# Ethernet.net
KiCad netlist of a schematic drawn in Altium Designer
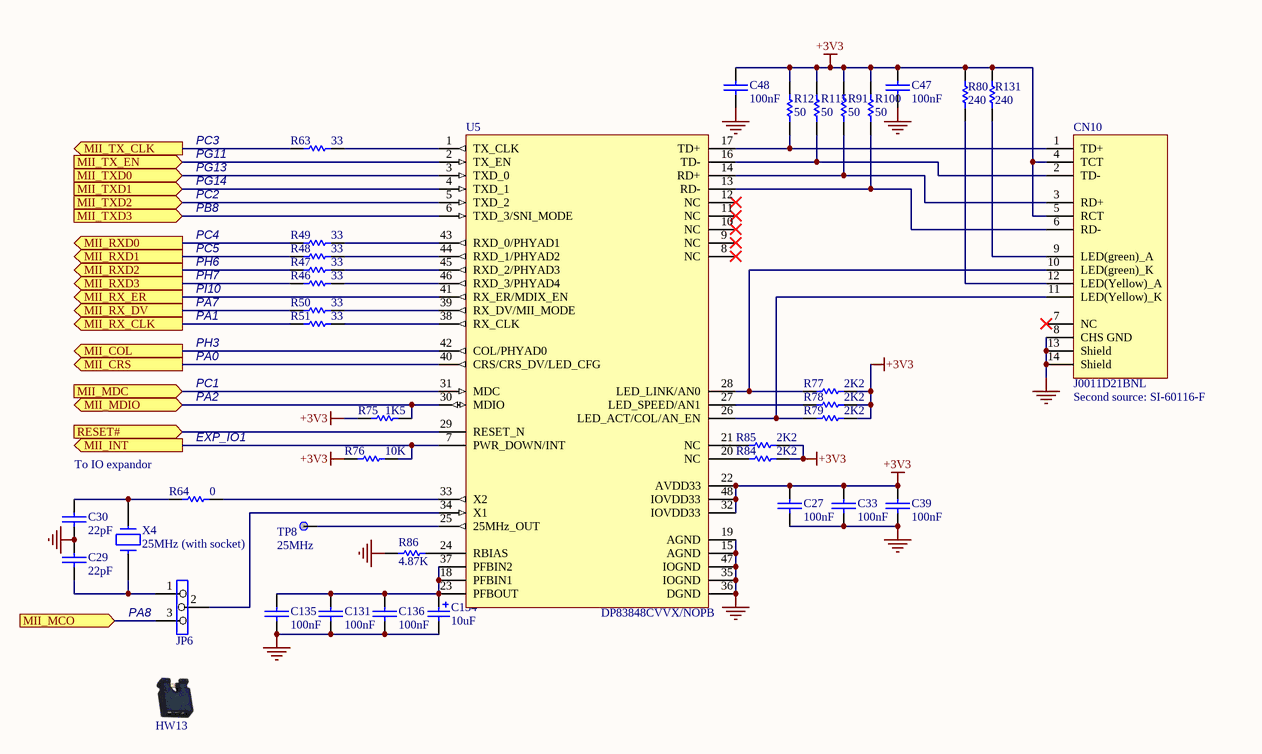
[diagram p0: Ethernet.SchDoc]

(export (version "E")
  (design (tool "Eeschema 10.0.6"))
  (components
    (comp (ref "C27")
      (value "100nF")
      (footprint "0603C")
      (description "Capacitor")
      (libsource (lib "*") (part "CAP"))
    )
    (comp (ref "C29")
      (value "22pF")
      (footprint "0603C")
      (description "Capacitor")
      (libsource (lib "*") (part "CAP"))
    )
    (comp (ref "C30")
      (value "22pF")
      (footprint "0603C")
      (description "Capacitor")
      (libsource (lib "*") (part "CAP"))
    )
    (comp (ref "C33")
      (value "100nF")
      (footprint "0603C")
      (description "Capacitor")
      (libsource (lib "*") (part "CAP"))
    )
    (comp (ref "C39")
      (value "100nF")
      (footprint "0603C")
      (description "Capacitor")
      (libsource (lib "*") (part "CAP"))
    )
    (comp (ref "C47")
      (value "100nF")
      (footprint "0603C")
      (description "Capacitor")
      (libsource (lib "*") (part "CAP"))
    )
    (comp (ref "C48")
      (value "100nF")
      (footprint "0603C")
      (description "Capacitor")
      (libsource (lib "*") (part "CAP"))
    )
    (comp (ref "C131")
      (value "100nF")
      (footprint "0603C")
      (description "Capacitor")
      (libsource (lib "*") (part "CAP"))
    )
    (comp (ref "C134")
      (value "10uF")
      (footprint "TAN-A")
      (description "Polarized Capacitor (Radial)")
      (fields (field (name "PUBLISHER") "Altium Limited"))
      (libsource (lib "Miscellaneous Devices") (part "Cap Pol1"))
    )
    (comp (ref "C135")
      (value "100nF")
      (footprint "0603C")
      (description "Capacitor")
      (libsource (lib "*") (part "CAP"))
    )
    (comp (ref "C136")
      (value "100nF")
      (footprint "0603C")
      (description "Capacitor")
      (libsource (lib "*") (part "CAP"))
    )
    (comp (ref "CN10")
      (value "J0011D21BNL")
      (footprint "RJ45_J0011D01BNL")
      (description "RJ45_connector, 8 pins, 1.27mm, RA, TH, Height 17.13mm")
      (libsource (lib "MB784") (part "J0011D21B"))
    )
    (comp (ref "HW13") (value "JUMPER_OPEN") (libsource (lib "mb1045") (part "JUMPER_OPEN")))
    (comp (ref "JP6") (value "~") (footprint "SIP3") (libsource (lib "STR910_SCHLIB") (part "Jumper3")))
    (comp (ref "R46")
      (value "33")
      (footprint "0603R")
      (description "Resistor")
      (fields (field (name "PUBLISHER") "Altium Limited"))
      (libsource (lib "Miscellaneous Devices") (part "Res1"))
    )
    (comp (ref "R47")
      (value "33")
      (footprint "0603R")
      (description "Resistor")
      (fields (field (name "PUBLISHER") "Altium Limited"))
      (libsource (lib "Miscellaneous Devices") (part "Res1"))
    )
    (comp (ref "R48")
      (value "33")
      (footprint "0603R")
      (description "Resistor")
      (fields (field (name "PUBLISHER") "Altium Limited"))
      (libsource (lib "Miscellaneous Devices") (part "Res1"))
    )
    (comp (ref "R49")
      (value "33")
      (footprint "0603R")
      (description "Resistor")
      (fields (field (name "PUBLISHER") "Altium Limited"))
      (libsource (lib "Miscellaneous Devices") (part "Res1"))
    )
    (comp (ref "R50")
      (value "33")
      (footprint "0603R")
      (description "Resistor")
      (fields (field (name "PUBLISHER") "Altium Limited"))
      (libsource (lib "Miscellaneous Devices") (part "Res1"))
    )
    (comp (ref "R51")
      (value "33")
      (footprint "0603R")
      (description "Resistor")
      (fields (field (name "PUBLISHER") "Altium Limited"))
      (libsource (lib "Miscellaneous Devices") (part "Res1"))
    )
    (comp (ref "R63")
      (value "33")
      (footprint "0603R")
      (description "Resistor")
      (fields (field (name "PUBLISHER") "Altium Limited"))
      (libsource (lib "Miscellaneous Devices") (part "Res1"))
    )
    (comp (ref "R64")
      (value "0")
      (footprint "0603R")
      (description "Resistor")
      (fields (field (name "PUBLISHER") "Altium Limited"))
      (libsource (lib "Miscellaneous Devices") (part "Res1"))
    )
    (comp (ref "R75")
      (value "1K5")
      (footprint "0603R")
      (description "Resistor")
      (fields (field (name "PUBLISHER") "Altium Limited"))
      (libsource (lib "Miscellaneous Devices") (part "Res1"))
    )
    (comp (ref "R76")
      (value "10K")
      (footprint "0603R")
      (description "Resistor")
      (fields (field (name "PUBLISHER") "Altium Limited"))
      (libsource (lib "Miscellaneous Devices") (part "Res1"))
    )
    (comp (ref "R77")
      (value "2K2")
      (footprint "0603R")
      (description "Resistor")
      (fields (field (name "PUBLISHER") "Altium Limited"))
      (libsource (lib "Miscellaneous Devices") (part "Res1"))
    )
    (comp (ref "R78")
      (value "2K2")
      (footprint "0603R")
      (description "Resistor")
      (fields (field (name "PUBLISHER") "Altium Limited"))
      (libsource (lib "Miscellaneous Devices") (part "Res1"))
    )
    (comp (ref "R79")
      (value "2K2")
      (footprint "0603R")
      (description "Resistor")
      (fields (field (name "PUBLISHER") "Altium Limited"))
      (libsource (lib "Miscellaneous Devices") (part "Res1"))
    )
    (comp (ref "R80")
      (value "240")
      (footprint "0603R")
      (description "Resistor")
      (fields (field (name "PUBLISHER") "Altium Limited"))
      (libsource (lib "Miscellaneous Devices") (part "Res1"))
    )
    (comp (ref "R84")
      (value "2K2")
      (footprint "0603R")
      (description "Resistor")
      (fields (field (name "PUBLISHER") "Altium Limited"))
      (libsource (lib "Miscellaneous Devices") (part "Res1"))
    )
    (comp (ref "R85")
      (value "2K2")
      (footprint "0603R")
      (description "Resistor")
      (fields (field (name "PUBLISHER") "Altium Limited"))
      (libsource (lib "Miscellaneous Devices") (part "Res1"))
    )
    (comp (ref "R86")
      (value "4.87K")
      (footprint "0603R")
      (description "Resistor")
      (fields (field (name "PUBLISHER") "Altium Limited"))
      (libsource (lib "Miscellaneous Devices") (part "Res1"))
    )
    (comp (ref "R91")
      (value "50")
      (footprint "0603R")
      (description "Resistor")
      (fields (field (name "PUBLISHER") "Altium Limited"))
      (libsource (lib "Miscellaneous Devices") (part "Res1"))
    )
    (comp (ref "R100")
      (value "50")
      (footprint "0603R")
      (description "Resistor")
      (fields (field (name "PUBLISHER") "Altium Limited"))
      (libsource (lib "Miscellaneous Devices") (part "Res1"))
    )
    (comp (ref "R115")
      (value "50")
      (footprint "0603R")
      (description "Resistor")
      (fields (field (name "PUBLISHER") "Altium Limited"))
      (libsource (lib "Miscellaneous Devices") (part "Res1"))
    )
    (comp (ref "R121")
      (value "50")
      (footprint "0603R")
      (description "Resistor")
      (fields (field (name "PUBLISHER") "Altium Limited"))
      (libsource (lib "Miscellaneous Devices") (part "Res1"))
    )
    (comp (ref "R131")
      (value "240")
      (footprint "0603R")
      (description "Resistor")
      (fields (field (name "PUBLISHER") "Altium Limited"))
      (libsource (lib "Miscellaneous Devices") (part "Res1"))
    )
    (comp (ref "TP8") (value "25MHz") (footprint "TP") (libsource (lib "*") (part "TP")))
    (comp (ref "U5")
      (value "DP83848CVVX/NOPB")
      (footprint "LQFP48_0R5_9X9")
      (libsource (lib "MB784") (part "DP83848CVV"))
    )
    (comp (ref "X4")
      (value "25MHz (with socket)")
      (footprint "XTAL_socket")
      (description "Crystal")
      (libsource (lib "*") (part "CRYSTAL"))
    )
  )
  (nets
    (net (code "1") (name "+3V3") (class "Default")
      (node (ref "C27") (pin "1") (pinfunction "1_1") (pintype "passive"))
      (node (ref "C33") (pin "2") (pinfunction "2_2") (pintype "passive"))
      (node (ref "C39") (pin "2") (pinfunction "2_2") (pintype "passive"))
      (node (ref "C47") (pin "2") (pinfunction "2_2") (pintype "passive"))
      (node (ref "C48") (pin "2") (pinfunction "2_2") (pintype "passive"))
      (node (ref "CN10") (pin "4") (pinfunction "TCT_4") (pintype "passive"))
      (node (ref "CN10") (pin "5") (pinfunction "RCT_5") (pintype "passive"))
      (node (ref "R100") (pin "1") (pinfunction "1_1") (pintype "passive"))
      (node (ref "R115") (pin "1") (pinfunction "1_1") (pintype "passive"))
      (node (ref "R121") (pin "1") (pinfunction "1_1") (pintype "passive"))
      (node (ref "R131") (pin "2") (pinfunction "2_2") (pintype "passive"))
      (node (ref "R75") (pin "2") (pinfunction "2_2") (pintype "passive"))
      (node (ref "R76") (pin "1") (pinfunction "1_1") (pintype "passive"))
      (node (ref "R77") (pin "2") (pinfunction "2_2") (pintype "passive"))
      (node (ref "R78") (pin "2") (pinfunction "2_2") (pintype "passive"))
      (node (ref "R79") (pin "2") (pinfunction "2_2") (pintype "passive"))
      (node (ref "R80") (pin "2") (pinfunction "2_2") (pintype "passive"))
      (node (ref "R84") (pin "2") (pinfunction "2_2") (pintype "passive"))
      (node (ref "R85") (pin "2") (pinfunction "2_2") (pintype "passive"))
      (node (ref "R91") (pin "1") (pinfunction "1_1") (pintype "passive"))
      (node (ref "U5") (pin "22") (pinfunction "AVDD33_22") (pintype "passive"))
      (node (ref "U5") (pin "32") (pinfunction "IOVDD33_32") (pintype "passive"))
      (node (ref "U5") (pin "48") (pinfunction "IOVDD33_48") (pintype "passive"))
    )
    (net (code "2") (name "/MII_COL") (class "Default")
      (node (ref "U5") (pin "42") (pinfunction "COL/PHYAD0_42") (pintype "output"))
    )
    (net (code "3") (name "/MII_CRS") (class "Default")
      (node (ref "U5") (pin "40") (pinfunction "CRS/CRS_DV/LED_CFG_40") (pintype "output"))
    )
    (net (code "4") (name "/MII_INT") (class "Default")
      (node (ref "R76") (pin "2") (pinfunction "2_2") (pintype "passive"))
      (node (ref "U5") (pin "7") (pinfunction "PWR_DOWN/INT_7") (pintype "passive"))
    )
    (net (code "5") (name "/MII_MCO") (class "Default") (node (ref "JP6") (pin "3") (pintype "passive")))
    (net (code "6") (name "/MII_MDC") (class "Default")
      (node (ref "U5") (pin "31") (pinfunction "MDC_31") (pintype "input"))
    )
    (net (code "7") (name "/MII_MDIO") (class "Default")
      (node (ref "R75") (pin "1") (pinfunction "1_1") (pintype "passive"))
      (node (ref "U5") (pin "30") (pinfunction "MDIO_30") (pintype "bidirectional"))
    )
    (net (code "8") (name "/MII_RXD0") (class "Default")
      (node (ref "R49") (pin "2") (pinfunction "2_2") (pintype "passive"))
    )
    (net (code "9") (name "/MII_RXD1") (class "Default")
      (node (ref "R48") (pin "2") (pinfunction "2_2") (pintype "passive"))
    )
    (net (code "10") (name "/MII_RXD2") (class "Default")
      (node (ref "R47") (pin "2") (pinfunction "2_2") (pintype "passive"))
    )
    (net (code "11") (name "/MII_RXD3") (class "Default")
      (node (ref "R46") (pin "2") (pinfunction "2_2") (pintype "passive"))
    )
    (net (code "12") (name "/MII_RX_CLK") (class "Default")
      (node (ref "R51") (pin "2") (pinfunction "2_2") (pintype "passive"))
    )
    (net (code "13") (name "/MII_RX_DV") (class "Default")
      (node (ref "R50") (pin "2") (pinfunction "2_2") (pintype "passive"))
    )
    (net (code "14") (name "/MII_RX_ER") (class "Default")
      (node (ref "U5") (pin "41") (pinfunction "RX_ER/MDIX_EN_41") (pintype "output"))
    )
    (net (code "15") (name "/MII_TXD0") (class "Default")
      (node (ref "U5") (pin "3") (pinfunction "TXD_0_3") (pintype "input"))
    )
    (net (code "16") (name "/MII_TXD1") (class "Default")
      (node (ref "U5") (pin "4") (pinfunction "TXD_1_4") (pintype "input"))
    )
    (net (code "17") (name "/MII_TXD2") (class "Default")
      (node (ref "U5") (pin "5") (pinfunction "TXD_2_5") (pintype "input"))
    )
    (net (code "18") (name "/MII_TXD3") (class "Default")
      (node (ref "U5") (pin "6") (pinfunction "TXD_3/SNI_MODE_6") (pintype "input"))
    )
    (net (code "19") (name "/MII_TX_CLK") (class "Default")
      (node (ref "R63") (pin "2") (pinfunction "2_2") (pintype "passive"))
    )
    (net (code "20") (name "/MII_TX_EN") (class "Default")
      (node (ref "U5") (pin "2") (pinfunction "TX_EN_2") (pintype "input"))
    )
    (net (code "21") (name "/RESET#") (class "Default")
      (node (ref "U5") (pin "29") (pinfunction "RESET_N_29") (pintype "passive"))
    )
    (net (code "22") (name "GND") (class "Default")
      (node (ref "C131") (pin "1") (pinfunction "1_1") (pintype "passive"))
      (node (ref "C134") (pin "2") (pinfunction "2_2") (pintype "passive"))
      (node (ref "C135") (pin "2") (pinfunction "2_2") (pintype "passive"))
      (node (ref "C136") (pin "1") (pinfunction "1_1") (pintype "passive"))
      (node (ref "C27") (pin "2") (pinfunction "2_2") (pintype "passive"))
      (node (ref "C29") (pin "2") (pinfunction "2_2") (pintype "passive"))
      (node (ref "C30") (pin "1") (pinfunction "1_1") (pintype "passive"))
      (node (ref "C33") (pin "1") (pinfunction "1_1") (pintype "passive"))
      (node (ref "C39") (pin "1") (pinfunction "1_1") (pintype "passive"))
      (node (ref "C47") (pin "1") (pinfunction "1_1") (pintype "passive"))
      (node (ref "C48") (pin "1") (pinfunction "1_1") (pintype "passive"))
      (node (ref "CN10") (pin "13") (pinfunction "Shield_13") (pintype "passive"))
      (node (ref "CN10") (pin "14") (pinfunction "Shield_14") (pintype "passive"))
      (node (ref "CN10") (pin "8") (pinfunction "CHS_GND_8") (pintype "passive"))
      (node (ref "R86") (pin "1") (pinfunction "1_1") (pintype "passive"))
      (node (ref "U5") (pin "15") (pinfunction "AGND_15") (pintype "passive"))
      (node (ref "U5") (pin "19") (pinfunction "AGND_19") (pintype "passive"))
      (node (ref "U5") (pin "35") (pinfunction "IOGND_35") (pintype "passive"))
      (node (ref "U5") (pin "36") (pinfunction "DGND_36") (pintype "passive"))
      (node (ref "U5") (pin "47") (pinfunction "IOGND_47") (pintype "passive"))
    )
    (net (code "23") (name "Net-(C29-Pad1)") (class "Default")
      (node (ref "C29") (pin "1") (pinfunction "1_1") (pintype "passive"))
      (node (ref "JP6") (pin "1") (pintype "passive"))
      (node (ref "X4") (pin "1") (pinfunction "1_1") (pintype "passive"))
    )
    (net (code "24") (name "Net-(C30-Pad2)") (class "Default")
      (node (ref "C30") (pin "2") (pinfunction "2_2") (pintype "passive"))
      (node (ref "R64") (pin "2") (pinfunction "2_2") (pintype "passive"))
      (node (ref "X4") (pin "2") (pinfunction "2_2") (pintype "passive"))
    )
    (net (code "25") (name "Net-(CN10-LED(Yellow)_A)") (class "Default")
      (node (ref "CN10") (pin "12") (pinfunction "LED(Yellow)_A_12") (pintype "passive"))
      (node (ref "R80") (pin "1") (pinfunction "1_1") (pintype "passive"))
    )
    (net (code "26") (name "Net-(CN10-LED(Yellow)_K)") (class "Default")
      (node (ref "CN10") (pin "11") (pinfunction "LED(Yellow)_K_11") (pintype "passive"))
      (node (ref "R79") (pin "1") (pinfunction "1_1") (pintype "passive"))
      (node (ref "U5") (pin "26") (pinfunction "LED_ACT/COL/AN_EN_26") (pintype "passive"))
    )
    (net (code "27") (name "Net-(CN10-LED(green)_A)") (class "Default")
      (node (ref "CN10") (pin "9") (pinfunction "LED(green)_A_9") (pintype "passive"))
      (node (ref "R131") (pin "1") (pinfunction "1_1") (pintype "passive"))
    )
    (net (code "28") (name "Net-(CN10-LED(green)_K)") (class "Default")
      (node (ref "CN10") (pin "10") (pinfunction "LED(green)_K_10") (pintype "passive"))
      (node (ref "R77") (pin "1") (pinfunction "1_1") (pintype "passive"))
      (node (ref "U5") (pin "28") (pinfunction "LED_LINK/AN0_28") (pintype "passive"))
    )
    (net (code "29") (name "Net-(CN10-RD+)") (class "Default")
      (node (ref "CN10") (pin "3") (pinfunction "RD+_3") (pintype "passive"))
      (node (ref "R91") (pin "2") (pinfunction "2_2") (pintype "passive"))
      (node (ref "U5") (pin "14") (pinfunction "RD+_14") (pintype "passive"))
    )
    (net (code "30") (name "Net-(CN10-RD-)") (class "Default")
      (node (ref "CN10") (pin "6") (pinfunction "RD-_6") (pintype "passive"))
      (node (ref "R100") (pin "2") (pinfunction "2_2") (pintype "passive"))
      (node (ref "U5") (pin "13") (pinfunction "RD-_13") (pintype "passive"))
    )
    (net (code "31") (name "Net-(CN10-TD+)") (class "Default")
      (node (ref "CN10") (pin "1") (pinfunction "TD+_1") (pintype "passive"))
      (node (ref "R121") (pin "2") (pinfunction "2_2") (pintype "passive"))
      (node (ref "U5") (pin "17") (pinfunction "TD+_17") (pintype "passive"))
    )
    (net (code "32") (name "Net-(CN10-TD-)") (class "Default")
      (node (ref "CN10") (pin "2") (pinfunction "TD-_2") (pintype "passive"))
      (node (ref "R115") (pin "2") (pinfunction "2_2") (pintype "passive"))
      (node (ref "U5") (pin "16") (pinfunction "TD-_16") (pintype "passive"))
    )
    (net (code "33") (name "Net-(R84-Pad1)") (class "Default")
      (node (ref "R84") (pin "1") (pinfunction "1_1") (pintype "passive"))
      (node (ref "U5") (pin "20") (pinfunction "NC_20") (pintype "passive"))
    )
    (net (code "34") (name "Net-(R85-Pad1)") (class "Default")
      (node (ref "R85") (pin "1") (pinfunction "1_1") (pintype "passive"))
      (node (ref "U5") (pin "21") (pinfunction "NC_21") (pintype "passive"))
    )
    (net (code "35") (name "Net-(U5-25MHz_OUT)") (class "Default")
      (node (ref "TP8") (pin "1") (pinfunction "1_1") (pintype "passive"))
      (node (ref "U5") (pin "25") (pinfunction "25MHz_OUT_25") (pintype "output"))
    )
    (net (code "36") (name "Net-(U5-LED_SPEED{slash}AN1)") (class "Default")
      (node (ref "R78") (pin "1") (pinfunction "1_1") (pintype "passive"))
      (node (ref "U5") (pin "27") (pinfunction "LED_SPEED/AN1_27") (pintype "passive"))
    )
    (net (code "37") (name "Net-(U5-PFBIN1)") (class "Default")
      (node (ref "C131") (pin "2") (pinfunction "2_2") (pintype "passive"))
      (node (ref "C134") (pin "1") (pinfunction "1_1") (pintype "passive"))
      (node (ref "C135") (pin "1") (pinfunction "1_1") (pintype "passive"))
      (node (ref "C136") (pin "2") (pinfunction "2_2") (pintype "passive"))
      (node (ref "U5") (pin "18") (pinfunction "PFBIN1_18") (pintype "passive"))
      (node (ref "U5") (pin "23") (pinfunction "PFBOUT_23") (pintype "passive"))
      (node (ref "U5") (pin "37") (pinfunction "PFBIN2_37") (pintype "passive"))
    )
    (net (code "38") (name "Net-(U5-RBIAS)") (class "Default")
      (node (ref "R86") (pin "2") (pinfunction "2_2") (pintype "passive"))
      (node (ref "U5") (pin "24") (pinfunction "RBIAS_24") (pintype "passive"))
    )
    (net (code "39") (name "Net-(U5-RXD_0{slash}PHYAD1)") (class "Default")
      (node (ref "R49") (pin "1") (pinfunction "1_1") (pintype "passive"))
      (node (ref "U5") (pin "43") (pinfunction "RXD_0/PHYAD1_43") (pintype "output"))
    )
    (net (code "40") (name "Net-(U5-RXD_1{slash}PHYAD2)") (class "Default")
      (node (ref "R48") (pin "1") (pinfunction "1_1") (pintype "passive"))
      (node (ref "U5") (pin "44") (pinfunction "RXD_1/PHYAD2_44") (pintype "output"))
    )
    (net (code "41") (name "Net-(U5-RXD_2{slash}PHYAD3)") (class "Default")
      (node (ref "R47") (pin "1") (pinfunction "1_1") (pintype "passive"))
      (node (ref "U5") (pin "45") (pinfunction "RXD_2/PHYAD3_45") (pintype "output"))
    )
    (net (code "42") (name "Net-(U5-RXD_3{slash}PHYAD4)") (class "Default")
      (node (ref "R46") (pin "1") (pinfunction "1_1") (pintype "passive"))
      (node (ref "U5") (pin "46") (pinfunction "RXD_3/PHYAD4_46") (pintype "output"))
    )
    (net (code "43") (name "Net-(U5-RX_CLK)") (class "Default")
      (node (ref "R51") (pin "1") (pinfunction "1_1") (pintype "passive"))
      (node (ref "U5") (pin "38") (pinfunction "RX_CLK_38") (pintype "output"))
    )
    (net (code "44") (name "Net-(U5-RX_DV{slash}MII_MODE)") (class "Default")
      (node (ref "R50") (pin "1") (pinfunction "1_1") (pintype "passive"))
      (node (ref "U5") (pin "39") (pinfunction "RX_DV/MII_MODE_39") (pintype "output"))
    )
    (net (code "45") (name "Net-(U5-TX_CLK)") (class "Default")
      (node (ref "R63") (pin "1") (pinfunction "1_1") (pintype "passive"))
      (node (ref "U5") (pin "1") (pinfunction "TX_CLK_1") (pintype "output"))
    )
    (net (code "46") (name "Net-(U5-X1)") (class "Default")
      (node (ref "JP6") (pin "2") (pintype "passive"))
      (node (ref "U5") (pin "34") (pinfunction "X1_34") (pintype "input"))
    )
    (net (code "47") (name "Net-(U5-X2)") (class "Default")
      (node (ref "R64") (pin "1") (pinfunction "1_1") (pintype "passive"))
      (node (ref "U5") (pin "33") (pinfunction "X2_33") (pintype "output"))
    )
    (net (code "48") (name "unconnected-(CN10-NC-Pad7)") (class "Default")
      (node (ref "CN10") (pin "7") (pinfunction "NC_7") (pintype "passive+no_connect"))
    )
    (net (code "49") (name "unconnected-(U5-NC-Pad8)") (class "Default")
      (node (ref "U5") (pin "8") (pinfunction "NC_8") (pintype "passive+no_connect"))
    )
    (net (code "50") (name "unconnected-(U5-NC-Pad9)") (class "Default")
      (node (ref "U5") (pin "9") (pinfunction "NC_9") (pintype "passive+no_connect"))
    )
    (net (code "51") (name "unconnected-(U5-NC-Pad10)") (class "Default")
      (node (ref "U5") (pin "10") (pinfunction "NC_10") (pintype "passive+no_connect"))
    )
    (net (code "52") (name "unconnected-(U5-NC-Pad11)") (class "Default")
      (node (ref "U5") (pin "11") (pinfunction "NC_11") (pintype "passive+no_connect"))
    )
    (net (code "53") (name "unconnected-(U5-NC-Pad12)") (class "Default")
      (node (ref "U5") (pin "12") (pinfunction "NC_12") (pintype "passive+no_connect"))
    )
  )
)
